# audio2.net
KiCad netlist of a schematic drawn in Altium Designer
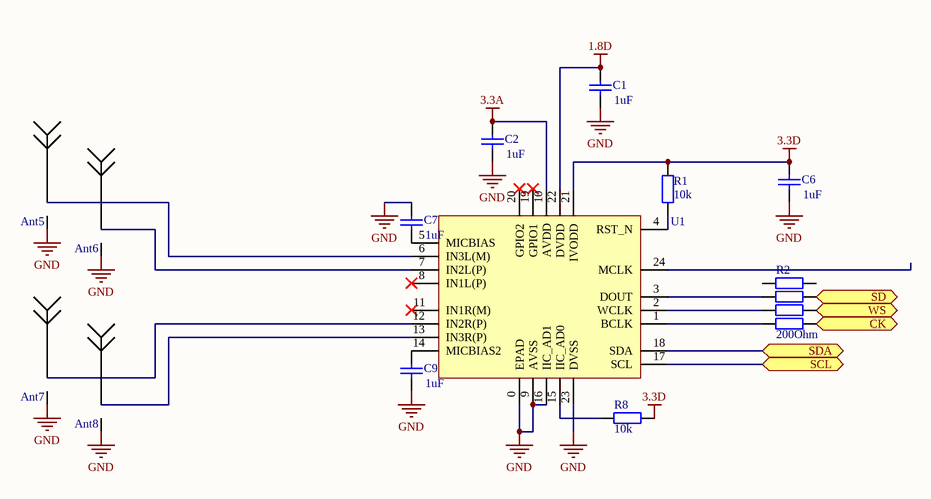
[diagram p0: audio2.SchDoc]

(export (version "E")
  (design (tool "Eeschema 10.0.6"))
  (components
    (comp (ref "Ant5") (value "Antenna") (footprint "BK5811:SMA") (libsource (lib "F4SDR") (part "Antenna")))
    (comp (ref "Ant6") (value "Antenna") (footprint "BK5811:SMA") (libsource (lib "F4SDR") (part "Antenna")))
    (comp (ref "Ant7") (value "Antenna") (footprint "BK5811:SMA") (libsource (lib "F4SDR") (part "Antenna")))
    (comp (ref "Ant8") (value "Antenna") (footprint "BK5811:SMA") (libsource (lib "F4SDR") (part "Antenna")))
    (comp (ref "C1")
      (value "1uF")
      (footprint "0402")
      (description "Capacitor")
      (libsource (lib "RTC6705") (part "Cap"))
    )
    (comp (ref "C2")
      (value "1uF")
      (footprint "0402")
      (description "Capacitor")
      (libsource (lib "RTC6705") (part "Cap"))
    )
    (comp (ref "C6")
      (value "1uF")
      (footprint "0402")
      (description "Capacitor")
      (libsource (lib "RTC6705") (part "Cap"))
    )
    (comp (ref "C7")
      (value "1uF")
      (footprint "0402")
      (description "Capacitor")
      (libsource (lib "RTC6705") (part "Cap"))
    )
    (comp (ref "C9")
      (value "1uF")
      (footprint "0402")
      (description "Capacitor")
      (libsource (lib "RTC6705") (part "Cap"))
    )
    (comp (ref "R1")
      (value "10k")
      (footprint "0402")
      (description "Resistor")
      (fields (field (name "Comment") "Res2") (field (name "PUBLISHER") "Altium Limited"))
      (libsource (lib "RTC6705") (part "Res2"))
    )
    (comp (ref "R2")
      (value "200Ohm")
      (footprint "0402X4")
      (description "Resistor")
      (fields (field (name "Comment") "Res*4") (field (name "PUBLISHER") "Altium Limited"))
      (libsource (lib "sch") (part "Res*4"))
    )
    (comp (ref "R8")
      (value "10k")
      (footprint "0402")
      (description "Resistor")
      (fields (field (name "Comment") "Res2") (field (name "PUBLISHER") "Altium Limited"))
      (libsource (lib "") (part "Res2_1"))
    )
    (comp (ref "U1")
      (value "TLV320ADC3101")
      (footprint "TLV320ADC3101")
      (libsource (lib "ADAU1761") (part "TLV320ADC3101"))
    )
  )
  (nets
    (net (code "1") (name "/CK") (class "Default")
      (node (ref "R2") (pin "5") (pinfunction "5_5") (pintype "passive"))
    )
    (net (code "2") (name "/SCL") (class "Default")
      (node (ref "U1") (pin "17") (pinfunction "SCL_17") (pintype "passive"))
    )
    (net (code "3") (name "/SD") (class "Default")
      (node (ref "R2") (pin "7") (pinfunction "7_7") (pintype "passive"))
    )
    (net (code "4") (name "/SDA") (class "Default")
      (node (ref "U1") (pin "18") (pinfunction "SDA_18") (pintype "passive"))
    )
    (net (code "5") (name "/WS") (class "Default")
      (node (ref "R2") (pin "6") (pinfunction "6_6") (pintype "passive"))
    )
    (net (code "6") (name "1.8D") (class "Default")
      (node (ref "C1") (pin "2") (pinfunction "2_2") (pintype "passive"))
      (node (ref "U1") (pin "22") (pinfunction "DVDD_22") (pintype "passive"))
    )
    (net (code "7") (name "3.3A") (class "Default")
      (node (ref "C2") (pin "2") (pinfunction "2_2") (pintype "passive"))
      (node (ref "U1") (pin "10") (pinfunction "AVDD_10") (pintype "passive"))
    )
    (net (code "8") (name "3.3D") (class "Default")
      (node (ref "C6") (pin "2") (pinfunction "2_2") (pintype "passive"))
      (node (ref "R1") (pin "2") (pinfunction "2_2") (pintype "passive"))
      (node (ref "R8") (pin "1") (pinfunction "1_1") (pintype "passive"))
      (node (ref "U1") (pin "21") (pinfunction "IVODD_21") (pintype "passive"))
    )
    (net (code "9") (name "GND") (class "Default")
      (node (ref "Ant5") (pin "GND") (pinfunction "G_GND") (pintype "passive"))
      (node (ref "Ant6") (pin "GND") (pinfunction "G_GND") (pintype "passive"))
      (node (ref "Ant7") (pin "GND") (pinfunction "G_GND") (pintype "passive"))
      (node (ref "Ant8") (pin "GND") (pinfunction "G_GND") (pintype "passive"))
      (node (ref "C1") (pin "1") (pinfunction "1_1") (pintype "passive"))
      (node (ref "C2") (pin "1") (pinfunction "1_1") (pintype "passive"))
      (node (ref "C6") (pin "1") (pinfunction "1_1") (pintype "passive"))
      (node (ref "C7") (pin "2") (pinfunction "2_2") (pintype "passive"))
      (node (ref "C9") (pin "1") (pinfunction "1_1") (pintype "passive"))
      (node (ref "U1") (pin "0") (pinfunction "EPAD_0") (pintype "passive"))
      (node (ref "U1") (pin "16") (pinfunction "IIC_AD1_16") (pintype "passive"))
      (node (ref "U1") (pin "23") (pinfunction "DVSS_23") (pintype "passive"))
      (node (ref "U1") (pin "9") (pinfunction "AVSS_9") (pintype "passive"))
    )
    (net (code "10") (name "Net-(U1-BCLK)") (class "Default")
      (node (ref "R2") (pin "4") (pinfunction "4_4") (pintype "passive"))
      (node (ref "U1") (pin "1") (pinfunction "BCLK_1") (pintype "passive"))
    )
    (net (code "11") (name "Net-(U1-DOUT)") (class "Default")
      (node (ref "R2") (pin "2") (pinfunction "2_2") (pintype "passive"))
      (node (ref "U1") (pin "3") (pinfunction "DOUT_3") (pintype "passive"))
    )
    (net (code "12") (name "Net-(U1-IIC_AD0)") (class "Default")
      (node (ref "R8") (pin "2") (pinfunction "2_2") (pintype "passive"))
      (node (ref "U1") (pin "15") (pinfunction "IIC_AD0_15") (pintype "passive"))
    )
    (net (code "13") (name "Net-(U1-IN2L(P))") (class "Default")
      (node (ref "Ant6") (pin "1") (pinfunction "1_1") (pintype "passive"))
      (node (ref "U1") (pin "7") (pinfunction "IN2L(P)_7") (pintype "passive"))
    )
    (net (code "14") (name "Net-(U1-IN2R(P))") (class "Default")
      (node (ref "Ant7") (pin "1") (pinfunction "1_1") (pintype "passive"))
      (node (ref "U1") (pin "12") (pinfunction "IN2R(P)_12") (pintype "passive"))
    )
    (net (code "15") (name "Net-(U1-IN3L(M))") (class "Default")
      (node (ref "Ant5") (pin "1") (pinfunction "1_1") (pintype "passive"))
      (node (ref "U1") (pin "6") (pinfunction "IN3L(M)_6") (pintype "passive"))
    )
    (net (code "16") (name "Net-(U1-IN3R(P))") (class "Default")
      (node (ref "Ant8") (pin "1") (pinfunction "1_1") (pintype "passive"))
      (node (ref "U1") (pin "13") (pinfunction "IN3R(P)_13") (pintype "passive"))
    )
    (net (code "17") (name "Net-(U1-MICBIAS)") (class "Default")
      (node (ref "C7") (pin "1") (pinfunction "1_1") (pintype "passive"))
      (node (ref "U1") (pin "5") (pinfunction "MICBIAS_5") (pintype "passive"))
    )
    (net (code "18") (name "Net-(U1-MICBIAS2)") (class "Default")
      (node (ref "C9") (pin "2") (pinfunction "2_2") (pintype "passive"))
      (node (ref "U1") (pin "14") (pinfunction "MICBIAS2_14") (pintype "passive"))
    )
    (net (code "19") (name "Net-(U1-RST_N)") (class "Default")
      (node (ref "R1") (pin "1") (pinfunction "1_1") (pintype "passive"))
      (node (ref "U1") (pin "4") (pinfunction "RST_N_4") (pintype "passive"))
    )
    (net (code "20") (name "Net-(U1-WCLK)") (class "Default")
      (node (ref "R2") (pin "3") (pinfunction "3_3") (pintype "passive"))
      (node (ref "U1") (pin "2") (pinfunction "WCLK_2") (pintype "passive"))
    )
    (net (code "21") (name "unconnected-(R2-Pad1)") (class "Default")
      (node (ref "R2") (pin "1") (pinfunction "1_1") (pintype "passive"))
    )
    (net (code "22") (name "unconnected-(R2-Pad8)") (class "Default")
      (node (ref "R2") (pin "8") (pinfunction "8_8") (pintype "passive"))
    )
    (net (code "23") (name "unconnected-(U1-GPIO1-Pad19)") (class "Default")
      (node (ref "U1") (pin "19") (pinfunction "GPIO1_19") (pintype "passive+no_connect"))
    )
    (net (code "24") (name "unconnected-(U1-GPIO2-Pad20)") (class "Default")
      (node (ref "U1") (pin "20") (pinfunction "GPIO2_20") (pintype "passive+no_connect"))
    )
    (net (code "25") (name "unconnected-(U1-IN1L(P)-Pad8)") (class "Default")
      (node (ref "U1") (pin "8") (pinfunction "IN1L(P)_8") (pintype "passive+no_connect"))
    )
    (net (code "26") (name "unconnected-(U1-IN1R(M)-Pad11)") (class "Default")
      (node (ref "U1") (pin "11") (pinfunction "IN1R(M)_11") (pintype "passive+no_connect"))
    )
    (net (code "27") (name "unconnected-(U1-MCLK-Pad24)") (class "Default")
      (node (ref "U1") (pin "24") (pinfunction "MCLK_24") (pintype "passive"))
    )
  )
)
